# Temperatura.net
KiCad netlist of a schematic drawn in Altium Designer
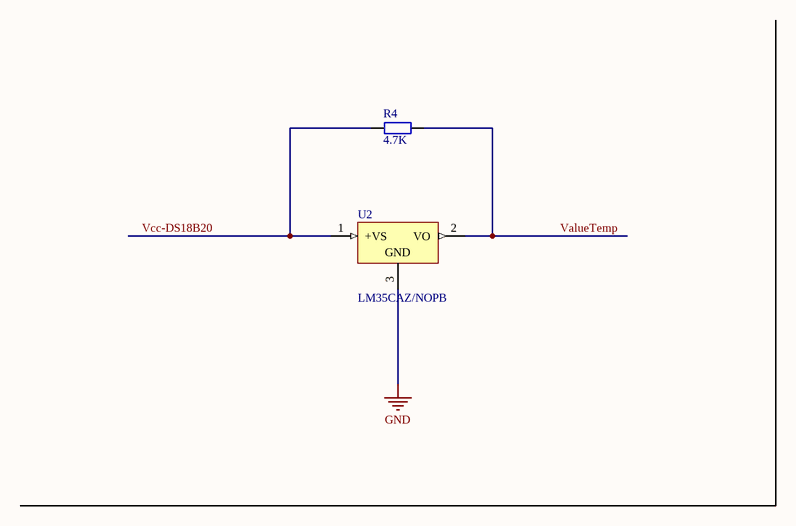
[diagram p0: Temperatura.SchDoc]

(export (version "E")
  (design (tool "Eeschema 10.0.6"))
  (components
    (comp (ref "R4")
      (value "4.7K")
      (footprint "R1206-0.55")
      (description "Resistor, generic")
      (fields (field (name "Comment") "R"))
      (libsource (lib "IFS_Altium") (part "R"))
    )
    (comp (ref "U2")
      (value "LM35CAZ/NOPB")
      (footprint "Z03A")
      (description "Precision Centigrade Temperature Sensor, 3-pin TO-92, Pb-Free")
      (fields
        (field (name "MANUFACTURER") "National Semiconductor")
        (field (name "PUBLISHER") "Altium Limited")
      )
      (libsource (lib "NSC Temperature Sensor") (part "LM35CAZ/NOPB"))
    )
  )
  (nets
    (net (code "1") (name "/ValueTemp") (class "Default")
      (node (ref "R4") (pin "1") (pinfunction "1_1") (pintype "passive"))
      (node (ref "U2") (pin "2") (pinfunction "VO_2") (pintype "output"))
    )
    (net (code "2") (name "/Vcc-DS18B20") (class "Default")
      (node (ref "R4") (pin "2") (pinfunction "2_2") (pintype "passive"))
      (node (ref "U2") (pin "1") (pinfunction "+VS_1") (pintype "input"))
    )
    (net (code "3") (name "GND") (class "Default")
      (node (ref "U2") (pin "3") (pinfunction "GND_3") (pintype "power_in"))
    )
  )
)
